# tris.net
KiCad netlist of a schematic drawn in EAGLE
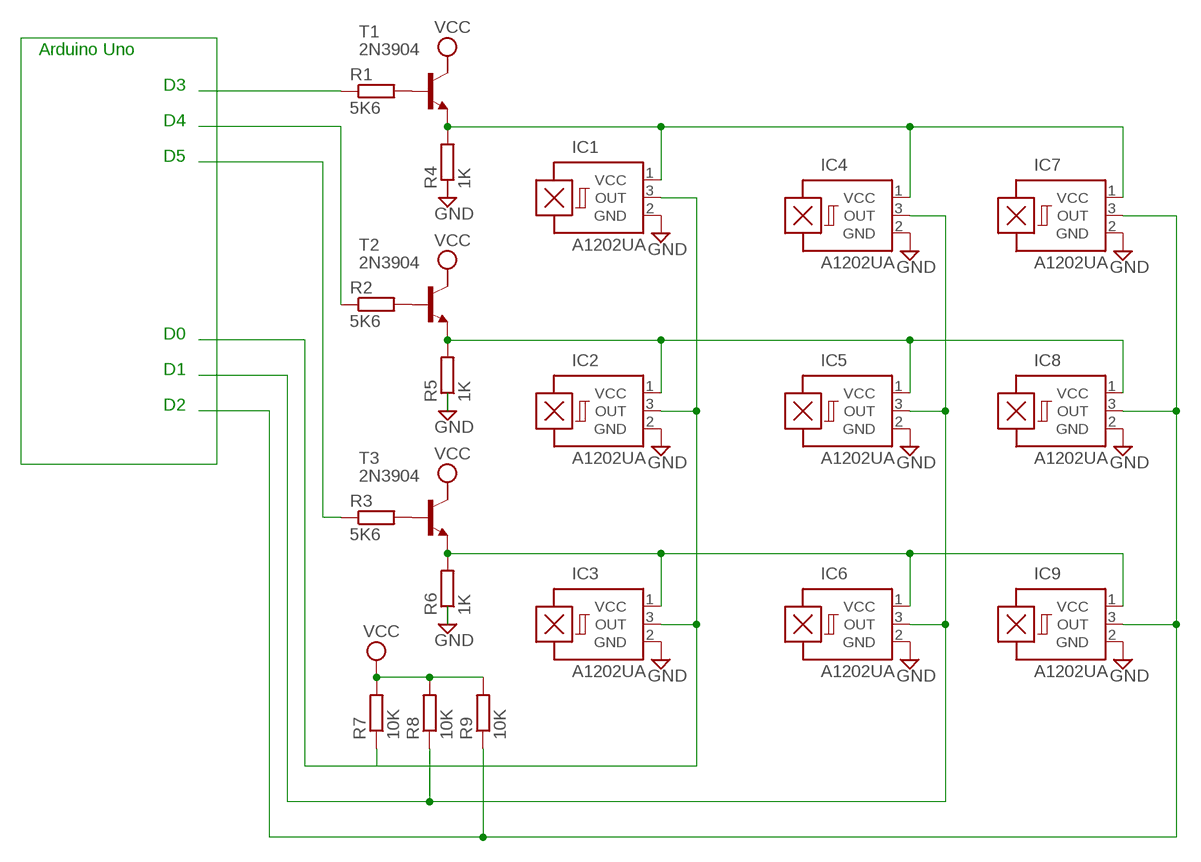
[diagram p0: schematic, sheet 1]

(export (version "E")
  (design (tool "Eeschema 10.0.6"))
  (components
    (comp (ref "IC1")
      (value "A1202UA")
      (footprint "eagle-import:SIP3-UA")
      (libsource (lib "eagle-import") (part "A12?UA02"))
    )
    (comp (ref "IC2")
      (value "A1202UA")
      (footprint "eagle-import:SIP3-UA")
      (libsource (lib "eagle-import") (part "A12?UA02"))
    )
    (comp (ref "IC3")
      (value "A1202UA")
      (footprint "eagle-import:SIP3-UA")
      (libsource (lib "eagle-import") (part "A12?UA02"))
    )
    (comp (ref "IC4")
      (value "A1202UA")
      (footprint "eagle-import:SIP3-UA")
      (libsource (lib "eagle-import") (part "A12?UA02"))
    )
    (comp (ref "IC5")
      (value "A1202UA")
      (footprint "eagle-import:SIP3-UA")
      (libsource (lib "eagle-import") (part "A12?UA02"))
    )
    (comp (ref "IC6")
      (value "A1202UA")
      (footprint "eagle-import:SIP3-UA")
      (libsource (lib "eagle-import") (part "A12?UA02"))
    )
    (comp (ref "IC7")
      (value "A1202UA")
      (footprint "eagle-import:SIP3-UA")
      (libsource (lib "eagle-import") (part "A12?UA02"))
    )
    (comp (ref "IC8")
      (value "A1202UA")
      (footprint "eagle-import:SIP3-UA")
      (libsource (lib "eagle-import") (part "A12?UA02"))
    )
    (comp (ref "IC9")
      (value "A1202UA")
      (footprint "eagle-import:SIP3-UA")
      (libsource (lib "eagle-import") (part "A12?UA02"))
    )
    (comp (ref "R1")
      (value "5K6")
      (footprint "eagle-import:0204_7")
      (libsource (lib "eagle-import") (part "R-EU_0204/7"))
    )
    (comp (ref "R2")
      (value "5K6")
      (footprint "eagle-import:0204_7")
      (libsource (lib "eagle-import") (part "R-EU_0204/7"))
    )
    (comp (ref "R3")
      (value "5K6")
      (footprint "eagle-import:0204_7")
      (libsource (lib "eagle-import") (part "R-EU_0204/7"))
    )
    (comp (ref "R4")
      (value "1K")
      (footprint "eagle-import:0204_7")
      (libsource (lib "eagle-import") (part "R-EU_0204/7"))
    )
    (comp (ref "R5")
      (value "1K")
      (footprint "eagle-import:0204_7")
      (libsource (lib "eagle-import") (part "R-EU_0204/7"))
    )
    (comp (ref "R6")
      (value "1K")
      (footprint "eagle-import:0204_7")
      (libsource (lib "eagle-import") (part "R-EU_0204/7"))
    )
    (comp (ref "R7")
      (value "10K")
      (footprint "eagle-import:0204_7")
      (libsource (lib "eagle-import") (part "R-EU_0204/7"))
    )
    (comp (ref "R8")
      (value "10K")
      (footprint "eagle-import:0204_7")
      (libsource (lib "eagle-import") (part "R-EU_0204/7"))
    )
    (comp (ref "R9")
      (value "10K")
      (footprint "eagle-import:0204_7")
      (libsource (lib "eagle-import") (part "R-EU_0204/7"))
    )
    (comp (ref "T1")
      (value "2N3904")
      (footprint "eagle-import:TO92")
      (libsource (lib "eagle-import") (part "2N3904"))
    )
    (comp (ref "T2")
      (value "2N3904")
      (footprint "eagle-import:TO92")
      (libsource (lib "eagle-import") (part "2N3904"))
    )
    (comp (ref "T3")
      (value "2N3904")
      (footprint "eagle-import:TO92")
      (libsource (lib "eagle-import") (part "2N3904"))
    )
  )
  (nets
    (net (code "1") (name "GND") (class "Default")
      (node (ref "IC1") (pin "2") (pinfunction "GND_2") (pintype "power_in"))
      (node (ref "IC2") (pin "2") (pinfunction "GND_2") (pintype "power_in"))
      (node (ref "IC3") (pin "2") (pinfunction "GND_2") (pintype "power_in"))
      (node (ref "IC4") (pin "2") (pinfunction "GND_2") (pintype "power_in"))
      (node (ref "IC5") (pin "2") (pinfunction "GND_2") (pintype "power_in"))
      (node (ref "IC6") (pin "2") (pinfunction "GND_2") (pintype "power_in"))
      (node (ref "IC7") (pin "2") (pinfunction "GND_2") (pintype "power_in"))
      (node (ref "IC8") (pin "2") (pinfunction "GND_2") (pintype "power_in"))
      (node (ref "IC9") (pin "2") (pinfunction "GND_2") (pintype "power_in"))
      (node (ref "R5") (pin "1") (pinfunction "1_1") (pintype "passive"))
      (node (ref "R6") (pin "1") (pinfunction "1_1") (pintype "passive"))
    )
    (net (code "2") (name "Net-(IC1-OUT)") (class "Default")
      (node (ref "IC1") (pin "3") (pinfunction "OUT_3") (pintype "output"))
      (node (ref "IC2") (pin "3") (pinfunction "OUT_3") (pintype "output"))
      (node (ref "IC3") (pin "3") (pinfunction "OUT_3") (pintype "output"))
      (node (ref "R7") (pin "1") (pinfunction "1_1") (pintype "passive"))
    )
    (net (code "3") (name "Net-(IC1-VCC)") (class "Default")
      (node (ref "IC1") (pin "1") (pinfunction "VCC_1") (pintype "power_in"))
      (node (ref "IC4") (pin "1") (pinfunction "VCC_1") (pintype "power_in"))
      (node (ref "IC7") (pin "1") (pinfunction "VCC_1") (pintype "power_in"))
      (node (ref "R4") (pin "2") (pinfunction "2_2") (pintype "passive"))
      (node (ref "T1") (pin "3") (pinfunction "E_3") (pintype "passive"))
    )
    (net (code "4") (name "Net-(IC2-VCC)") (class "Default")
      (node (ref "IC2") (pin "1") (pinfunction "VCC_1") (pintype "power_in"))
      (node (ref "IC5") (pin "1") (pinfunction "VCC_1") (pintype "power_in"))
      (node (ref "IC8") (pin "1") (pinfunction "VCC_1") (pintype "power_in"))
      (node (ref "R5") (pin "2") (pinfunction "2_2") (pintype "passive"))
      (node (ref "T2") (pin "3") (pinfunction "E_3") (pintype "passive"))
    )
    (net (code "5") (name "Net-(IC3-VCC)") (class "Default")
      (node (ref "IC3") (pin "1") (pinfunction "VCC_1") (pintype "power_in"))
      (node (ref "IC6") (pin "1") (pinfunction "VCC_1") (pintype "power_in"))
      (node (ref "IC9") (pin "1") (pinfunction "VCC_1") (pintype "power_in"))
      (node (ref "R6") (pin "2") (pinfunction "2_2") (pintype "passive"))
      (node (ref "T3") (pin "3") (pinfunction "E_3") (pintype "passive"))
    )
    (net (code "6") (name "Net-(IC4-OUT)") (class "Default")
      (node (ref "IC4") (pin "3") (pinfunction "OUT_3") (pintype "output"))
      (node (ref "IC5") (pin "3") (pinfunction "OUT_3") (pintype "output"))
      (node (ref "IC6") (pin "3") (pinfunction "OUT_3") (pintype "output"))
      (node (ref "R8") (pin "1") (pinfunction "1_1") (pintype "passive"))
    )
    (net (code "7") (name "Net-(IC7-OUT)") (class "Default")
      (node (ref "IC7") (pin "3") (pinfunction "OUT_3") (pintype "output"))
      (node (ref "IC8") (pin "3") (pinfunction "OUT_3") (pintype "output"))
      (node (ref "IC9") (pin "3") (pinfunction "OUT_3") (pintype "output"))
      (node (ref "R9") (pin "1") (pinfunction "1_1") (pintype "passive"))
    )
    (net (code "8") (name "Net-(T1-B)") (class "Default")
      (node (ref "R1") (pin "2") (pinfunction "2_2") (pintype "passive"))
      (node (ref "T1") (pin "2") (pinfunction "B_2") (pintype "passive"))
    )
    (net (code "9") (name "Net-(T2-B)") (class "Default")
      (node (ref "R2") (pin "2") (pinfunction "2_2") (pintype "passive"))
      (node (ref "T2") (pin "2") (pinfunction "B_2") (pintype "passive"))
    )
    (net (code "10") (name "Net-(T3-B)") (class "Default")
      (node (ref "R3") (pin "2") (pinfunction "2_2") (pintype "passive"))
      (node (ref "T3") (pin "2") (pinfunction "B_2") (pintype "passive"))
    )
    (net (code "11") (name "VCC") (class "Default")
      (node (ref "R7") (pin "2") (pinfunction "2_2") (pintype "passive"))
      (node (ref "R8") (pin "2") (pinfunction "2_2") (pintype "passive"))
      (node (ref "R9") (pin "2") (pinfunction "2_2") (pintype "passive"))
    )
    (net (code "12") (name "unconnected-(R1-Pad1)") (class "Default")
      (node (ref "R1") (pin "1") (pinfunction "1_1") (pintype "passive"))
    )
    (net (code "13") (name "unconnected-(R2-Pad1)") (class "Default")
      (node (ref "R2") (pin "1") (pinfunction "1_1") (pintype "passive"))
    )
    (net (code "14") (name "unconnected-(R3-Pad1)") (class "Default")
      (node (ref "R3") (pin "1") (pinfunction "1_1") (pintype "passive"))
    )
    (net (code "15") (name "unconnected-(R4-Pad1)") (class "Default")
      (node (ref "R4") (pin "1") (pinfunction "1_1") (pintype "passive"))
    )
    (net (code "16") (name "unconnected-(T1-C-Pad1)") (class "Default")
      (node (ref "T1") (pin "1") (pinfunction "C_1") (pintype "passive"))
    )
    (net (code "17") (name "unconnected-(T2-C-Pad1)") (class "Default")
      (node (ref "T2") (pin "1") (pinfunction "C_1") (pintype "passive"))
    )
    (net (code "18") (name "unconnected-(T3-C-Pad1)") (class "Default")
      (node (ref "T3") (pin "1") (pinfunction "C_1") (pintype "passive"))
    )
  )
)
